# Cascade.net
KiCad netlist of a schematic drawn in Altium Designer
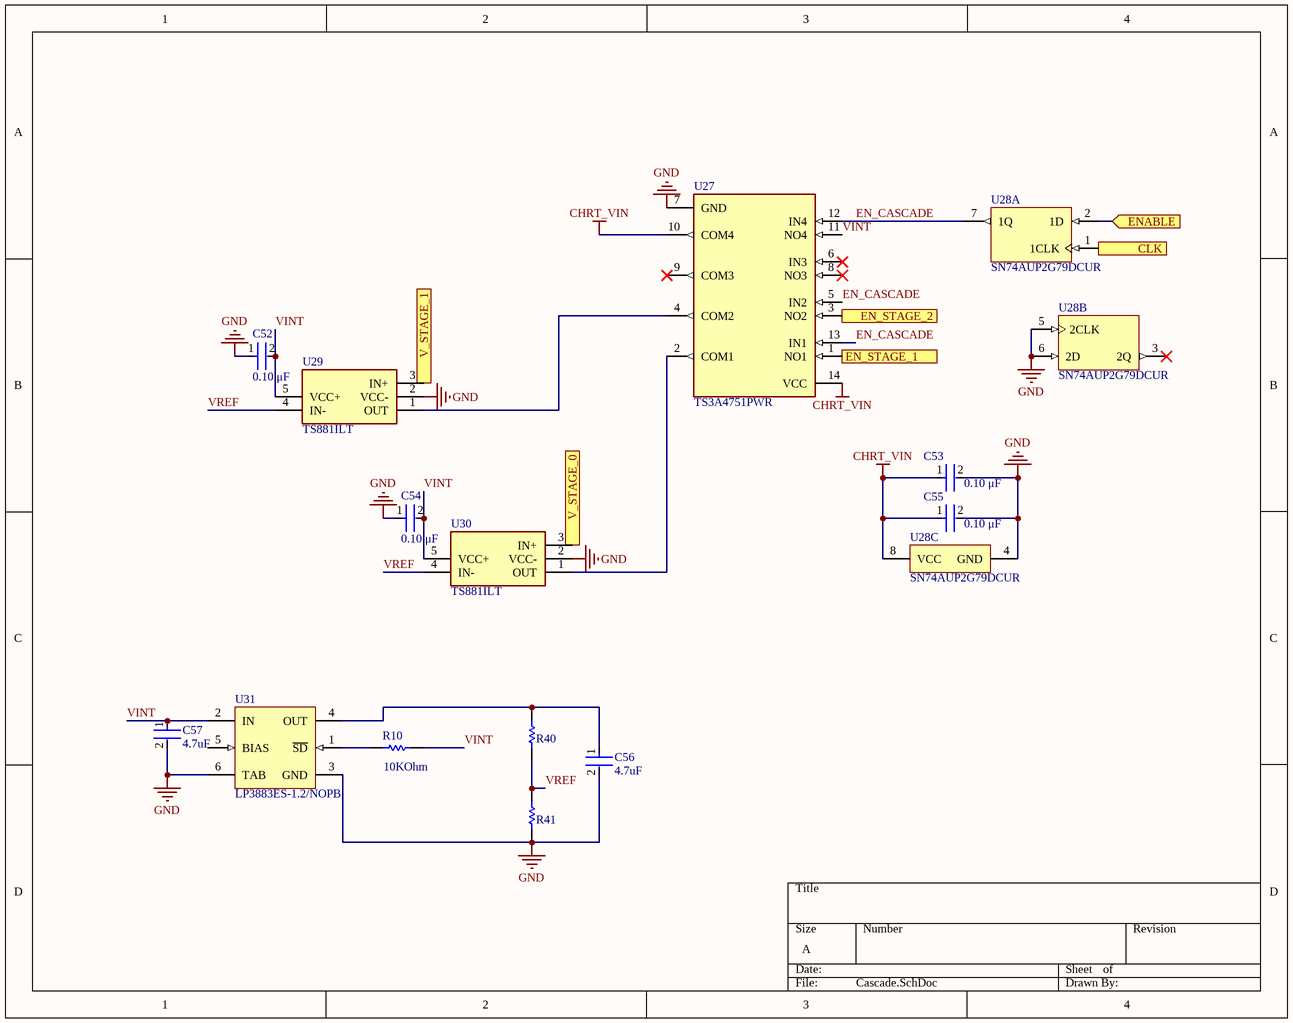
[diagram p0: Cascade.SchDoc]

(export (version "E")
  (design (tool "Eeschema 10.0.6"))
  (components
    (comp (ref "C52")
      (value "C0402C104K8PACTU")
      (footprint "FP-C0402-BB-MFG")
      (description "CAP CER 0.1UF 10V X5R 0402")
      (fields
        (field (name "CAPACITANCE") "0.10 μF")
        (field (name "MANUFACTURER") "Kemet")
        (field (name "TOLERANCE") "0.1")
      )
      (libsource (lib "Altium Content Vault") (part "b4654b650e69147ec39a6b967a45e02"))
    )
    (comp (ref "C53")
      (value "C0402C104K8PACTU")
      (footprint "FP-C0402-BB-MFG")
      (description "CAP CER 0.1UF 10V X5R 0402")
      (fields
        (field (name "CAPACITANCE") "0.10 μF")
        (field (name "MANUFACTURER") "Kemet")
        (field (name "TOLERANCE") "0.1")
      )
      (libsource (lib "Altium Content Vault") (part "b4654b650e69147ec39a6b967a45e02"))
    )
    (comp (ref "C54")
      (value "C0402C104K8PACTU")
      (footprint "FP-C0402-BB-MFG")
      (description "CAP CER 0.1UF 10V X5R 0402")
      (fields
        (field (name "CAPACITANCE") "0.10 μF")
        (field (name "MANUFACTURER") "Kemet")
        (field (name "TOLERANCE") "0.1")
      )
      (libsource (lib "Altium Content Vault") (part "b4654b650e69147ec39a6b967a45e02"))
    )
    (comp (ref "C55")
      (value "C0402C104K8PACTU")
      (footprint "FP-C0402-BB-MFG")
      (description "CAP CER 0.1UF 10V X5R 0402")
      (fields
        (field (name "CAPACITANCE") "0.10 μF")
        (field (name "MANUFACTURER") "Kemet")
        (field (name "TOLERANCE") "0.1")
      )
      (libsource (lib "Altium Content Vault") (part "b4654b650e69147ec39a6b967a45e02"))
    )
    (comp (ref "C56")
      (value "GRM155R60J475ME47D")
      (footprint "FP-GRM155-0_1-IPC_B")
      (description "Chip Multilayer Ceramic Capacitors for General Purpose, 0402, 4.7uF, X5R, 15%, 20%, 6.3V")
      (fields
        (field (name "VOLTAGE") "6.3V")
        (field (name "CAPACITANCE") "4.7uF")
        (field (name "TOLERANCE") "20%")
      )
      (libsource (lib "Altium Content Vault") (part "11868f565c42a9108669ba33697ecf6"))
    )
    (comp (ref "C57")
      (value "GRM155R60J475ME47D")
      (footprint "FP-GRM155-0_1-IPC_B")
      (description "Chip Multilayer Ceramic Capacitors for General Purpose, 0402, 4.7uF, X5R, 15%, 20%, 6.3V")
      (fields
        (field (name "VOLTAGE") "6.3V")
        (field (name "CAPACITANCE") "4.7uF")
        (field (name "TOLERANCE") "20%")
      )
      (libsource (lib "Altium Content Vault") (part "11868f565c42a9108669ba33697ecf6"))
    )
    (comp (ref "R10")
      (value "ERJ2RKF1002X")
      (footprint "RESC1005X40X25LL05T05")
      (description "Chip Resistor, 10 KOhm, +/- 1%, 0.1 W, -55 to 155 degC, 0402 (1005 Metric), RoHS, Tape and Reel")
      (fields
        (field (name "RESISTANCE") "10KOhm")
        (field (name "TOLERANCE") "1%")
        (field (name "MANUFACTURER") "Panasonic")
      )
      (libsource (lib "Altium Content Vault") (part "RES-2"))
    )
    (comp (ref "R40")
      (value "ERJ-2GEJ915X")
      (footprint "RESC1005X40X25LL05T05")
      (fields (field (name "MANUFACTURER") "Panasonic"))
      (libsource (lib "Altium Content Vault") (part "RES"))
    )
    (comp (ref "R41")
      (value "CRCW04022M40FKED")
      (footprint "RESC1005X40X25LL05T05")
      (fields (field (name "MANUFACTURER") "Vishay Dale"))
      (libsource (lib "Altium Content Vault") (part "RES"))
    )
    (comp (ref "U27")
      (value "TS3A4751PWR")
      (footprint "FP-PW0014A-IPC_C")
      (description "IC SWITCH QUAD SPST 14TSSOP")
      (libsource (lib "Altium Content Vault") (part "75fdcfb842d41a92b92a478e82e68ae"))
    )
    (comp (ref "U28")
      (value "SN74AUP2G79DCUR")
      (footprint "DCU0008A_L")
      (description "Low-Power Dual Positive-Edge-Triggered D-Type Flip-Flop, DCU0008A, LARGE T&R")
      (fields
        (field (name "MANUFACTURER") "Texas Instruments")
        (field (name "GENERIC PART NUMBER") "SN74AUP2G79")
      )
      (libsource (lib "Altium Content Vault") (part "TI-SN74XXX2G79-8_A"))
    )
    (comp (ref "U29")
      (value "TS881ILT")
      (footprint "SOT95P280X145-5N")
      (description "Integrated Circuit")
      (libsource (lib "Integrated_Library1") (part "TS881ILT"))
    )
    (comp (ref "U30")
      (value "TS881ILT")
      (footprint "SOT95P280X145-5N")
      (description "Integrated Circuit")
      (libsource (lib "Integrated_Library1") (part "TS881ILT"))
    )
    (comp (ref "U31")
      (value "LP3883ES-1.2/NOPB")
      (footprint "KTT0005B_M")
      (description "3A Fast-Response Ultra Low Dropout Linear Regulators, 5-pin TO-263, Pb-Free")
      (fields (field (name "MANUFACTURER") "Texas Instruments"))
      (libsource (lib "Altium Content Vault") (part "PM-REG-LP3881-SOT6"))
    )
  )
  (nets
    (net (code "1") (name "/CLK") (class "Default")
      (node (ref "U28") (pin "1") (pinfunction "1CLK_1") (pintype "input"))
    )
    (net (code "2") (name "/ENABLE") (class "Default")
      (node (ref "U28") (pin "2") (pinfunction "1D_2") (pintype "input"))
    )
    (net (code "3") (name "/EN_CASCADE") (class "Default")
      (node (ref "U27") (pin "12") (pinfunction "IN4_12") (pintype "input"))
      (node (ref "U27") (pin "13") (pinfunction "IN1_13") (pintype "input"))
      (node (ref "U27") (pin "5") (pinfunction "IN2_5") (pintype "input"))
      (node (ref "U28") (pin "7") (pinfunction "1Q_7") (pintype "output"))
    )
    (net (code "4") (name "/EN_STAGE_1") (class "Default")
      (node (ref "U27") (pin "1") (pinfunction "NO1_1") (pintype "input"))
    )
    (net (code "5") (name "/EN_STAGE_2") (class "Default")
      (node (ref "U27") (pin "3") (pinfunction "NO2_3") (pintype "input"))
    )
    (net (code "6") (name "/VINT") (class "Default")
      (node (ref "C52") (pin "2") (pinfunction "2_2") (pintype "passive"))
      (node (ref "C54") (pin "2") (pinfunction "2_2") (pintype "passive"))
      (node (ref "C57") (pin "1") (pinfunction "1_1") (pintype "passive"))
      (node (ref "R10") (pin "2") (pinfunction "2_2") (pintype "passive"))
      (node (ref "U27") (pin "11") (pinfunction "NO4_11") (pintype "input"))
      (node (ref "U29") (pin "5") (pinfunction "VCC+_5") (pintype "passive"))
      (node (ref "U30") (pin "5") (pinfunction "VCC+_5") (pintype "passive"))
      (node (ref "U31") (pin "2") (pinfunction "IN_2") (pintype "power_in"))
    )
    (net (code "7") (name "/VREF") (class "Default")
      (node (ref "R40") (pin "1") (pinfunction "1_1") (pintype "passive"))
      (node (ref "R41") (pin "1") (pinfunction "1_1") (pintype "passive"))
      (node (ref "U29") (pin "4") (pinfunction "IN-_4") (pintype "passive"))
      (node (ref "U30") (pin "4") (pinfunction "IN-_4") (pintype "passive"))
    )
    (net (code "8") (name "/V_STAGE_0") (class "Default")
      (node (ref "U30") (pin "3") (pinfunction "IN+_3") (pintype "passive"))
    )
    (net (code "9") (name "/V_STAGE_1") (class "Default")
      (node (ref "U29") (pin "3") (pinfunction "IN+_3") (pintype "passive"))
    )
    (net (code "10") (name "CHRT_VIN") (class "Default")
      (node (ref "C53") (pin "1") (pinfunction "1_1") (pintype "passive"))
      (node (ref "C55") (pin "1") (pinfunction "1_1") (pintype "passive"))
      (node (ref "U27") (pin "10") (pinfunction "COM4_10") (pintype "output"))
      (node (ref "U27") (pin "14") (pinfunction "VCC_14") (pintype "power_in"))
      (node (ref "U28") (pin "8") (pinfunction "VCC_8") (pintype "power_in"))
    )
    (net (code "11") (name "GND") (class "Default")
      (node (ref "C52") (pin "1") (pinfunction "1_1") (pintype "passive"))
      (node (ref "C53") (pin "2") (pinfunction "2_2") (pintype "passive"))
      (node (ref "C54") (pin "1") (pinfunction "1_1") (pintype "passive"))
      (node (ref "C55") (pin "2") (pinfunction "2_2") (pintype "passive"))
      (node (ref "C56") (pin "2") (pinfunction "2_2") (pintype "passive"))
      (node (ref "C57") (pin "2") (pinfunction "2_2") (pintype "passive"))
      (node (ref "R41") (pin "2") (pinfunction "2_2") (pintype "passive"))
      (node (ref "U27") (pin "7") (pinfunction "GND_7") (pintype "power_in"))
      (node (ref "U28") (pin "4") (pinfunction "GND_4") (pintype "power_in"))
      (node (ref "U28") (pin "5") (pinfunction "2CLK_5") (pintype "input"))
      (node (ref "U28") (pin "6") (pinfunction "2D_6") (pintype "input"))
      (node (ref "U29") (pin "2") (pinfunction "VCC-_2") (pintype "passive"))
      (node (ref "U30") (pin "2") (pinfunction "VCC-_2") (pintype "passive"))
      (node (ref "U31") (pin "3") (pinfunction "GND_3") (pintype "power_in"))
      (node (ref "U31") (pin "6") (pinfunction "TAB_6") (pintype "power_in"))
    )
    (net (code "12") (name "Net-(U27-COM1)") (class "Default")
      (node (ref "U27") (pin "2") (pinfunction "COM1_2") (pintype "output"))
      (node (ref "U30") (pin "1") (pinfunction "OUT_1") (pintype "passive"))
    )
    (net (code "13") (name "Net-(U27-COM2)") (class "Default")
      (node (ref "U27") (pin "4") (pinfunction "COM2_4") (pintype "output"))
      (node (ref "U29") (pin "1") (pinfunction "OUT_1") (pintype "passive"))
    )
    (net (code "14") (name "Net-(U31-OUT)") (class "Default")
      (node (ref "C56") (pin "1") (pinfunction "1_1") (pintype "passive"))
      (node (ref "R40") (pin "2") (pinfunction "2_2") (pintype "passive"))
      (node (ref "U31") (pin "4") (pinfunction "OUT_4") (pintype "power_in"))
    )
    (net (code "15") (name "Net-(U31-~{SD})") (class "Default")
      (node (ref "R10") (pin "1") (pinfunction "1_1") (pintype "passive"))
      (node (ref "U31") (pin "1") (pinfunction "~{SD}_1") (pintype "input"))
    )
    (net (code "16") (name "unconnected-(U27-COM3-Pad9)") (class "Default")
      (node (ref "U27") (pin "9") (pinfunction "COM3_9") (pintype "output+no_connect"))
    )
    (net (code "17") (name "unconnected-(U27-IN3-Pad6)") (class "Default")
      (node (ref "U27") (pin "6") (pinfunction "IN3_6") (pintype "input+no_connect"))
    )
    (net (code "18") (name "unconnected-(U27-NO3-Pad8)") (class "Default")
      (node (ref "U27") (pin "8") (pinfunction "NO3_8") (pintype "input+no_connect"))
    )
    (net (code "19") (name "unconnected-(U28B-2Q-Pad3)") (class "Default")
      (node (ref "U28") (pin "3") (pinfunction "2Q_3") (pintype "output+no_connect"))
    )
    (net (code "20") (name "unconnected-(U31-BIAS-Pad5)") (class "Default")
      (node (ref "U31") (pin "5") (pinfunction "BIAS_5") (pintype "input"))
    )
  )
)
